# reverse_polarity_protection.net
KiCad netlist of a schematic drawn in Altium Designer
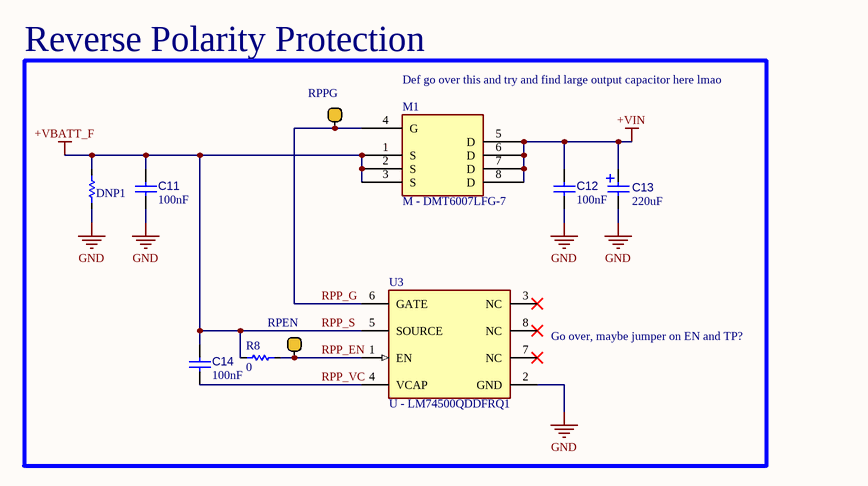
[diagram p0: reverse_polarity_protection.SchDoc]

(export (version "E")
  (design (tool "Eeschema 10.0.6"))
  (components
    (comp (ref "C11")
      (value "100nF")
      (footprint "CAP_0603")
      (description "GRM188R72A104KA35D - 0.1 µF ±10% 100V Ceramic Capacitor X7R 0603 (1608 Metric)")
      (fields (field (name "Comment") "C - CAP CER 100nF 100V 10% 0603"))
      (libsource (lib "power_board_schhlib") (part "C - CAP CER 100nF 100V 10% 0603"))
    )
    (comp (ref "C12")
      (value "100nF")
      (footprint "CAP_0603")
      (description "GRM188R72A104KA35D - 0.1 µF ±10% 100V Ceramic Capacitor X7R 0603 (1608 Metric)")
      (fields (field (name "Comment") "C - CAP CER 100nF 100V 10% 0603"))
      (libsource (lib "power_board_schhlib") (part "C - CAP CER 100nF 100V 10% 0603"))
    )
    (comp (ref "C13")
      (value "220uF")
      (footprint "C - 860020574012")
      (description "860020574012 - 220 µF 35 V Aluminum Electrolytic Capacitors Radial, Can 2000 Hrs @ 105°C")
      (fields (field (name "Comment") "860020574012"))
      (libsource (lib "power_board_schhlib") (part "C - CAP ELC 220uF 35V 20% CAN"))
    )
    (comp (ref "C14")
      (value "100nF")
      (footprint "CAP_0603")
      (description "GRM188R72A104KA35D - 0.1 µF ±10% 100V Ceramic Capacitor X7R 0603 (1608 Metric)")
      (fields (field (name "Comment") "C - CAP CER 100nF 100V 10% 0603"))
      (libsource (lib "power_board_schhlib") (part "C - CAP CER 100nF 100V 10% 0603"))
    )
    (comp (ref "DNP1")
      (value "DNP - DNP PAD 0603")
      (footprint "DNP 0603")
      (libsource (lib "power_board_schhlib") (part "DNP - DNP PAD 0603"))
    )
    (comp (ref "M1")
      (value "M - DMT6007LFG-7")
      (footprint "M - DMT6007LFG-7")
      (description "DMT6007LFG-7 - N-Channel 60 V 15A (Ta), 80A (Tc) 2.2W (Ta), 62.5W (Tc) Surface Mount POWERDI3333-8")
      (libsource (lib "power_board_schhlib") (part "M - DMT6007LFG-7"))
    )
    (comp (ref "R8")
      (value "0")
      (footprint "RES 0603")
      (description "ERJ-3GEY0R00V - 0 Ohms Jumper Chip Resistor 0603 (1608 Metric) Automotive AEC-Q200 Thick Film")
      (fields (field (name "Comment") "R - RES 0R 0.1W N/A% 0603"))
      (libsource (lib "power_board_schhlib") (part "R - RES 0R 0.1W N/A% 0603"))
    )
    (comp (ref "RPEN")
      (value "TP - SMD Pad Testpoint-Symbol-1")
      (footprint "TP - SMD Pad Testpoint")
      (description "Testpoint used for debugging and testing. SMD Pad")
      (libsource (lib "power_board_schhlib") (part "TP - SMD Pad Testpoint-Symbol-1"))
    )
    (comp (ref "RPPG")
      (value "TP - SMD Pad Testpoint-Symbol-1")
      (footprint "TP - SMD Pad Testpoint")
      (description "Testpoint used for debugging and testing. SMD Pad")
      (libsource (lib "power_board_schhlib") (part "TP - SMD Pad Testpoint-Symbol-1"))
    )
    (comp (ref "U3")
      (value "U - LM74500QDDFRQ1")
      (footprint "U - LM74500QDDFRQ1")
      (description "LM74500QDDFRQ1 - Battery Battery Protection IC TSOT-23-8")
      (libsource (lib "power_board_schhlib") (part "U - LM74500QDDFRQ1"))
    )
  )
  (nets
    (net (code "1") (name "+VBATT_F") (class "Default")
      (node (ref "C11") (pin "2") (pinfunction "2_2") (pintype "passive"))
      (node (ref "C14") (pin "2") (pinfunction "2_2") (pintype "passive"))
      (node (ref "DNP1") (pin "2") (pinfunction "2_2") (pintype "passive"))
      (node (ref "M1") (pin "1") (pinfunction "S_1") (pintype "passive"))
      (node (ref "M1") (pin "2") (pinfunction "S_2") (pintype "passive"))
      (node (ref "M1") (pin "3") (pinfunction "S_3") (pintype "passive"))
      (node (ref "R8") (pin "1") (pinfunction "1_1") (pintype "passive"))
      (node (ref "U3") (pin "5") (pinfunction "SOURCE_5") (pintype "passive"))
    )
    (net (code "2") (name "+VIN") (class "Default")
      (node (ref "C12") (pin "2") (pinfunction "2_2") (pintype "passive"))
      (node (ref "C13") (pin "1") (pinfunction "POS_1") (pintype "passive"))
      (node (ref "M1") (pin "5") (pinfunction "D_5") (pintype "passive"))
      (node (ref "M1") (pin "6") (pinfunction "D_6") (pintype "passive"))
      (node (ref "M1") (pin "7") (pinfunction "D_7") (pintype "passive"))
      (node (ref "M1") (pin "8") (pinfunction "D_8") (pintype "passive"))
    )
    (net (code "3") (name "/RPP_EN") (class "Default")
      (node (ref "R8") (pin "2") (pinfunction "2_2") (pintype "passive"))
      (node (ref "RPEN") (pin "1") (pinfunction "1_1") (pintype "passive"))
      (node (ref "U3") (pin "1") (pinfunction "EN_1") (pintype "input"))
    )
    (net (code "4") (name "/RPP_G") (class "Default")
      (node (ref "M1") (pin "4") (pinfunction "G_4") (pintype "passive"))
      (node (ref "RPPG") (pin "1") (pinfunction "1_1") (pintype "passive"))
      (node (ref "U3") (pin "6") (pinfunction "GATE_6") (pintype "passive"))
    )
    (net (code "5") (name "/RPP_VC") (class "Default")
      (node (ref "C14") (pin "1") (pinfunction "1_1") (pintype "passive"))
      (node (ref "U3") (pin "4") (pinfunction "VCAP_4") (pintype "passive"))
    )
    (net (code "6") (name "GND") (class "Default")
      (node (ref "C11") (pin "1") (pinfunction "1_1") (pintype "passive"))
      (node (ref "C12") (pin "1") (pinfunction "1_1") (pintype "passive"))
      (node (ref "C13") (pin "2") (pinfunction "NEG_2") (pintype "passive"))
      (node (ref "DNP1") (pin "1") (pinfunction "1_1") (pintype "passive"))
      (node (ref "U3") (pin "2") (pinfunction "GND_2") (pintype "power_in"))
    )
    (net (code "7") (name "unconnected-(U3-NC-Pad3)") (class "Default")
      (node (ref "U3") (pin "3") (pinfunction "NC_3") (pintype "passive+no_connect"))
    )
    (net (code "8") (name "unconnected-(U3-NC-Pad7)") (class "Default")
      (node (ref "U3") (pin "7") (pinfunction "NC_7") (pintype "passive+no_connect"))
    )
    (net (code "9") (name "unconnected-(U3-NC-Pad8)") (class "Default")
      (node (ref "U3") (pin "8") (pinfunction "NC_8") (pintype "passive+no_connect"))
    )
  )
)
